# Sheet1.net
KiCad netlist of a schematic drawn in Altium Designer
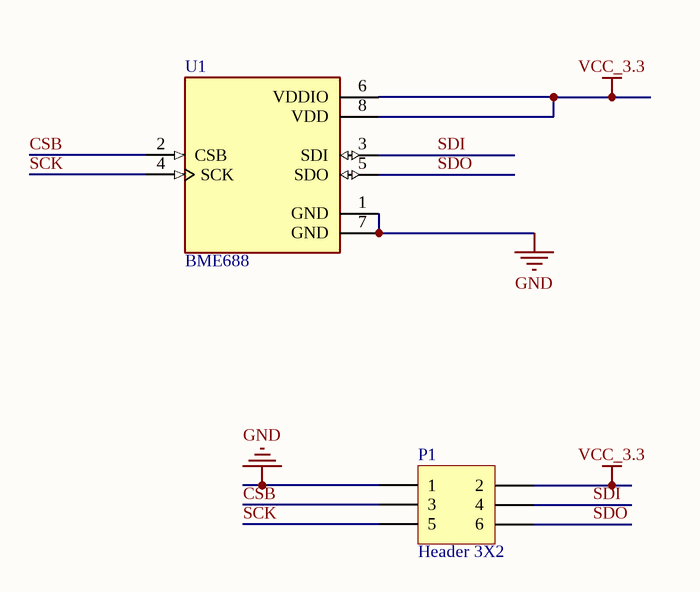
[diagram p0: Sheet1.SchDoc]

(export (version "E")
  (design (tool "Eeschema 10.0.6"))
  (components
    (comp (ref "P1")
      (value "Header 3X2")
      (footprint "HDR2X3")
      (description "Header 2x3")
      (fields (field (name "PUBLISHER") "Altium Limited"))
      (libsource (lib "Miscellaneous Connectors") (part "Header 3X2"))
    )
    (comp (ref "U1")
      (value "BME688")
      (footprint "IC_BME688")
      (description "Gas sensor measuring relative humidity, barometric pressure, ambient temperature and gas (VOC)")
      (fields (field (name "MF") "{'manufacturer': u'Bosch Sensortec'}"))
      (libsource (lib "SnapEDA_Library") (part "BME688"))
    )
  )
  (nets
    (net (code "1") (name "/CSB") (class "Default")
      (node (ref "P1") (pin "3") (pinfunction "3_3") (pintype "passive"))
      (node (ref "U1") (pin "2") (pinfunction "CSB_2") (pintype "input"))
    )
    (net (code "2") (name "/SCK") (class "Default")
      (node (ref "P1") (pin "5") (pinfunction "5_5") (pintype "passive"))
      (node (ref "U1") (pin "4") (pinfunction "SCK_4") (pintype "input"))
    )
    (net (code "3") (name "/SDI") (class "Default")
      (node (ref "P1") (pin "4") (pinfunction "4_4") (pintype "passive"))
      (node (ref "U1") (pin "3") (pinfunction "SDI_3") (pintype "bidirectional"))
    )
    (net (code "4") (name "/SDO") (class "Default")
      (node (ref "P1") (pin "6") (pinfunction "6_6") (pintype "passive"))
      (node (ref "U1") (pin "5") (pinfunction "SDO_5") (pintype "bidirectional"))
    )
    (net (code "5") (name "GND") (class "Default")
      (node (ref "P1") (pin "1") (pinfunction "1_1") (pintype "passive"))
      (node (ref "U1") (pin "1") (pinfunction "GND_1") (pintype "power_in"))
      (node (ref "U1") (pin "7") (pinfunction "GND_7") (pintype "power_in"))
    )
    (net (code "6") (name "VCC_3.3") (class "Default")
      (node (ref "P1") (pin "2") (pinfunction "2_2") (pintype "passive"))
      (node (ref "U1") (pin "6") (pinfunction "VDDIO_6") (pintype "power_in"))
      (node (ref "U1") (pin "8") (pinfunction "VDD_8") (pintype "power_in"))
    )
  )
)
